# MCU.net
KiCad netlist of a schematic drawn in Altium Designer
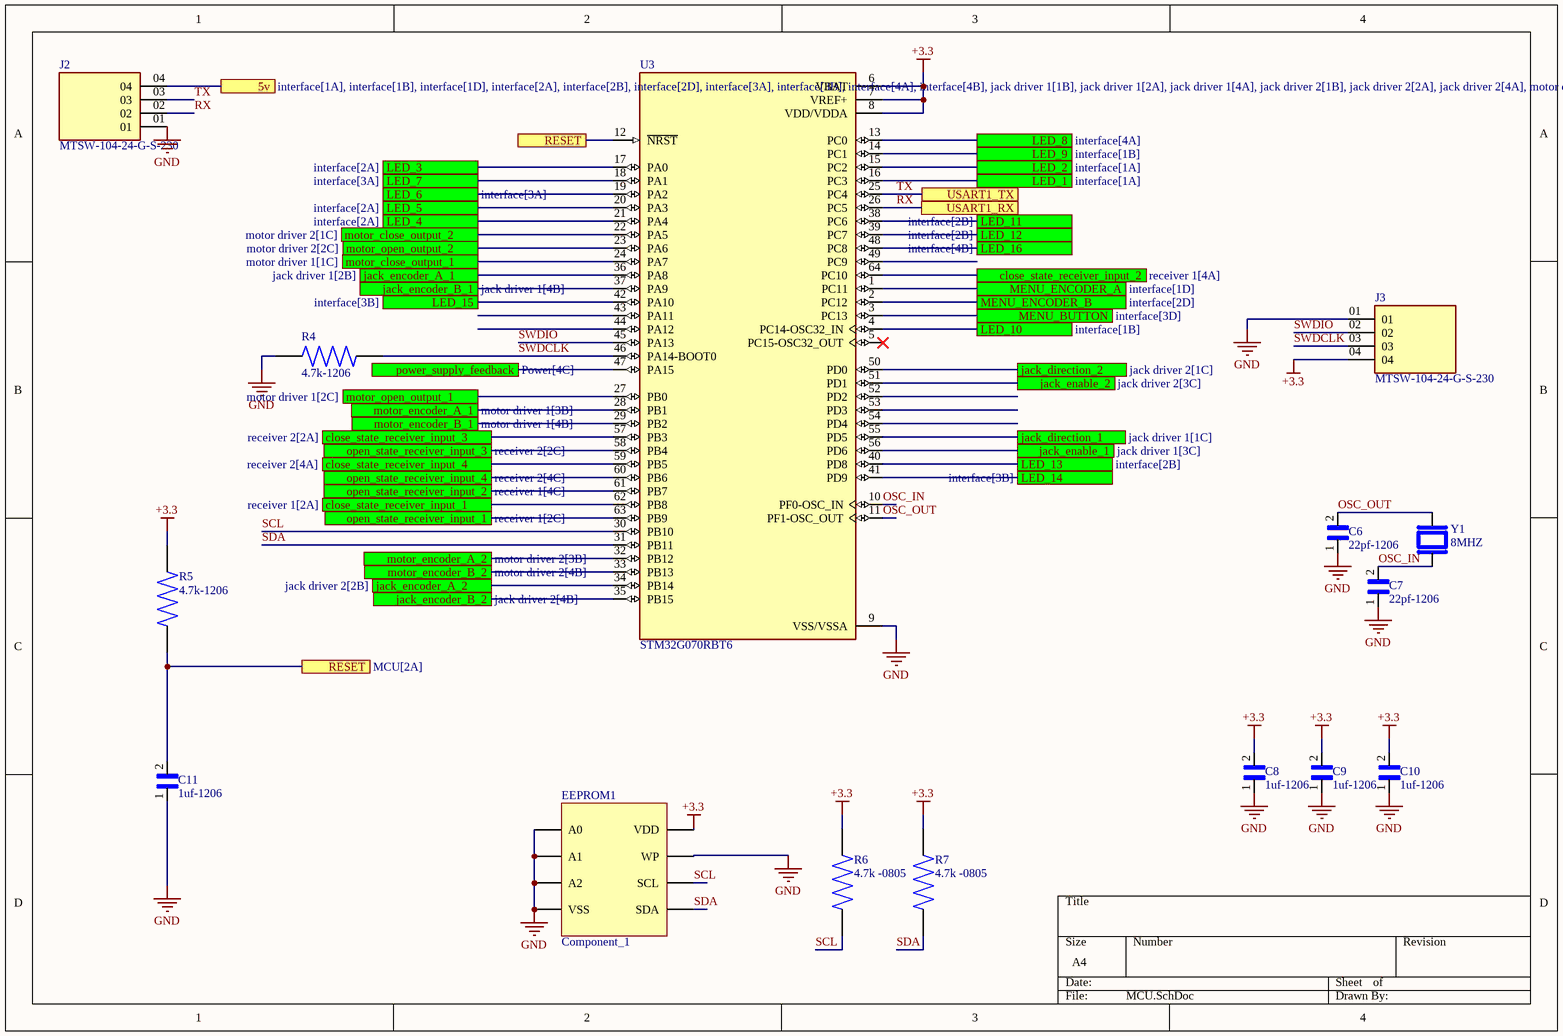
[diagram p0: MCU.SchDoc]

(export (version "E")
  (design (tool "Eeschema 10.0.6"))
  (components
    (comp (ref "C6")
      (value "22pf-1206")
      (footprint "CAPC3216X180N")
      (description "1ÂµF Â±20% 50V Ceramic Capacitor X8R 1206 (3216 Metric)")
      (fields (field (name "MF") "TDK") (field (name "MP") "CGA5L3X8R1H105M160AB"))
      (libsource (lib "cap-1206") (part "CGA5L3X8R1H105M160AB"))
    )
    (comp (ref "C7")
      (value "22pf-1206")
      (footprint "CAPC3216X180N")
      (description "1ÂµF Â±20% 50V Ceramic Capacitor X8R 1206 (3216 Metric)")
      (fields (field (name "MF") "TDK") (field (name "MP") "CGA5L3X8R1H105M160AB"))
      (libsource (lib "cap-1206") (part "CGA5L3X8R1H105M160AB"))
    )
    (comp (ref "C8")
      (value "1uf-1206")
      (footprint "CAPC3216X180N")
      (description "1ÂµF Â±20% 50V Ceramic Capacitor X8R 1206 (3216 Metric)")
      (fields (field (name "MF") "TDK") (field (name "MP") "CGA5L3X8R1H105M160AB"))
      (libsource (lib "cap-1206") (part "CGA5L3X8R1H105M160AB"))
    )
    (comp (ref "C9")
      (value "1uf-1206")
      (footprint "CAPC3216X180N")
      (description "1ÂµF Â±20% 50V Ceramic Capacitor X8R 1206 (3216 Metric)")
      (fields (field (name "MF") "TDK") (field (name "MP") "CGA5L3X8R1H105M160AB"))
      (libsource (lib "cap-1206") (part "CGA5L3X8R1H105M160AB"))
    )
    (comp (ref "C10")
      (value "1uf-1206")
      (footprint "CAPC3216X180N")
      (description "1ÂµF Â±20% 50V Ceramic Capacitor X8R 1206 (3216 Metric)")
      (fields (field (name "MF") "TDK") (field (name "MP") "CGA5L3X8R1H105M160AB"))
      (libsource (lib "cap-1206") (part "CGA5L3X8R1H105M160AB"))
    )
    (comp (ref "C11")
      (value "1uf-1206")
      (footprint "CAPC3216X180N")
      (description "1ÂµF Â±20% 50V Ceramic Capacitor X8R 1206 (3216 Metric)")
      (fields (field (name "MF") "TDK") (field (name "MP") "CGA5L3X8R1H105M160AB"))
      (libsource (lib "cap-1206") (part "CGA5L3X8R1H105M160AB"))
    )
    (comp (ref "EEPROM1")
      (value "Component_1")
      (footprint "SOIC127P602X172-8N")
      (libsource (lib "FM24CL64B") (part "Component_1"))
    )
    (comp (ref "J2")
      (value "MTSW-104-24-G-S-230")
      (footprint "SAMTEC_MTSW-104-24-G-S-230")
      (libsource (lib "4pin2.54mm") (part "MTSW-104-24-G-S-230"))
    )
    (comp (ref "J3")
      (value "MTSW-104-24-G-S-230")
      (footprint "SAMTEC_MTSW-104-24-G-S-230")
      (libsource (lib "") (part "MTSW-104-24-G-S-230_1"))
    )
    (comp (ref "R4")
      (value "4.7k-1206")
      (footprint "RESC3015X65N")
      (description "Res Thin Film 1206 10K Ohm 0.1% 1/8W Â±25ppm/Â°C Molded SMD SMD Paper T/R")
      (fields (field (name "MF") "TE Connectivity") (field (name "MP") "CPF1206B10KE1"))
      (libsource (lib "resistor-1206") (part "CPF1206B10KE1"))
    )
    (comp (ref "R5")
      (value "4.7k-1206")
      (footprint "RESC3015X65N")
      (description "Res Thin Film 1206 10K Ohm 0.1% 1/8W Â±25ppm/Â°C Molded SMD SMD Paper T/R")
      (fields (field (name "MF") "TE Connectivity") (field (name "MP") "CPF1206B10KE1"))
      (libsource (lib "resistor-1206") (part "CPF1206B10KE1"))
    )
    (comp (ref "R6")
      (value "4.7k -0805")
      (footprint "RESC2012X65N")
      (description "Fixed Resistor CRGCQ 0805 470R 5%")
      (fields (field (name "MF") "TE Connectivity") (field (name "MP") "CRGCQ0805J470R"))
      (libsource (lib "res0805") (part "CRGCQ0805J470R"))
    )
    (comp (ref "R7")
      (value "4.7k -0805")
      (footprint "RESC2012X65N")
      (description "Fixed Resistor CRGCQ 0805 470R 5%")
      (fields (field (name "MF") "TE Connectivity") (field (name "MP") "CRGCQ0805J470R"))
      (libsource (lib "res0805") (part "CRGCQ0805J470R"))
    )
    (comp (ref "U3")
      (value "STM32G070RBT6")
      (footprint "QFP50P1200X1200X160-64N")
      (fields (field (name "MF") "STMicroelectronics"))
      (libsource (lib "STM32G070RBT6") (part "STM32G070RBT6"))
    )
    (comp (ref "Y1")
      (value "8MHZ")
      (footprint "XTAL_ABLS2-12.000MHZ-D4Y-T")
      (description "HC/49US (AT49) LOW PROFILE SURFACE MOUNT MICROPROCESSOR CRYSTAL")
      (fields (field (name "MP") "ABLS2-12.000MHZ-D4Y-T") (field (name "MF") "Abracon"))
      (libsource (lib "CRYSTAL") (part "ABLS2-12.000MHZ-D4Y-T"))
    )
  )
  (nets
    (net (code "1") (name "+3.3") (class "Default")
      (node (ref "C10") (pin "2") (pinfunction "2_2") (pintype "passive"))
      (node (ref "C8") (pin "2") (pinfunction "2_2") (pintype "passive"))
      (node (ref "C9") (pin "2") (pinfunction "2_2") (pintype "passive"))
      (node (ref "EEPROM1") (pin "7") (pinfunction "VDD_7") (pintype "passive"))
      (node (ref "J3") (pin "04") (pinfunction "04_04") (pintype "passive"))
      (node (ref "R5") (pin "2") (pinfunction "2_2") (pintype "passive"))
      (node (ref "R6") (pin "2") (pinfunction "2_2") (pintype "passive"))
      (node (ref "R7") (pin "2") (pinfunction "2_2") (pintype "passive"))
      (node (ref "U3") (pin "6") (pinfunction "VBAT_6") (pintype "power_in"))
      (node (ref "U3") (pin "7") (pinfunction "VREF+_7") (pintype "power_in"))
      (node (ref "U3") (pin "8") (pinfunction "VDD/VDDA_8") (pintype "power_in"))
    )
    (net (code "2") (name "/5v") (class "Default")
      (node (ref "J2") (pin "04") (pinfunction "04_04") (pintype "passive"))
    )
    (net (code "3") (name "/LED_1") (class "Default")
      (node (ref "U3") (pin "16") (pinfunction "PC3_16") (pintype "bidirectional"))
    )
    (net (code "4") (name "/LED_2") (class "Default")
      (node (ref "U3") (pin "15") (pinfunction "PC2_15") (pintype "bidirectional"))
    )
    (net (code "5") (name "/LED_3") (class "Default")
      (node (ref "U3") (pin "17") (pinfunction "PA0_17") (pintype "bidirectional"))
    )
    (net (code "6") (name "/LED_4") (class "Default")
      (node (ref "U3") (pin "21") (pinfunction "PA4_21") (pintype "bidirectional"))
    )
    (net (code "7") (name "/LED_5") (class "Default")
      (node (ref "U3") (pin "20") (pinfunction "PA3_20") (pintype "bidirectional"))
    )
    (net (code "8") (name "/LED_6") (class "Default")
      (node (ref "U3") (pin "19") (pinfunction "PA2_19") (pintype "bidirectional"))
    )
    (net (code "9") (name "/LED_7") (class "Default")
      (node (ref "U3") (pin "18") (pinfunction "PA1_18") (pintype "bidirectional"))
    )
    (net (code "10") (name "/LED_8") (class "Default")
      (node (ref "U3") (pin "13") (pinfunction "PC0_13") (pintype "bidirectional"))
    )
    (net (code "11") (name "/LED_9") (class "Default")
      (node (ref "U3") (pin "14") (pinfunction "PC1_14") (pintype "bidirectional"))
    )
    (net (code "12") (name "/LED_10") (class "Default")
      (node (ref "U3") (pin "4") (pinfunction "PC14-OSC32_IN_4") (pintype "bidirectional"))
    )
    (net (code "13") (name "/LED_11") (class "Default")
      (node (ref "U3") (pin "38") (pinfunction "PC6_38") (pintype "bidirectional"))
    )
    (net (code "14") (name "/LED_12") (class "Default")
      (node (ref "U3") (pin "39") (pinfunction "PC7_39") (pintype "bidirectional"))
    )
    (net (code "15") (name "/LED_13") (class "Default")
      (node (ref "U3") (pin "40") (pinfunction "PD8_40") (pintype "bidirectional"))
    )
    (net (code "16") (name "/LED_14") (class "Default")
      (node (ref "U3") (pin "41") (pinfunction "PD9_41") (pintype "bidirectional"))
    )
    (net (code "17") (name "/LED_15") (class "Default")
      (node (ref "U3") (pin "42") (pinfunction "PA10_42") (pintype "bidirectional"))
    )
    (net (code "18") (name "/LED_16") (class "Default")
      (node (ref "U3") (pin "48") (pinfunction "PC8_48") (pintype "bidirectional"))
    )
    (net (code "19") (name "/MENU_BUTTON") (class "Default")
      (node (ref "U3") (pin "3") (pinfunction "PC13_3") (pintype "bidirectional"))
    )
    (net (code "20") (name "/MENU_ENCODER_A") (class "Default")
      (node (ref "U3") (pin "1") (pinfunction "PC11_1") (pintype "bidirectional"))
    )
    (net (code "21") (name "/MENU_ENCODER_B") (class "Default")
      (node (ref "U3") (pin "2") (pinfunction "PC12_2") (pintype "bidirectional"))
    )
    (net (code "22") (name "/OSC_IN") (class "Default")
      (node (ref "C7") (pin "2") (pinfunction "2_2") (pintype "passive"))
      (node (ref "U3") (pin "10") (pinfunction "PF0-OSC_IN_10") (pintype "bidirectional"))
      (node (ref "Y1") (pin "1") (pinfunction "1_1") (pintype "passive"))
    )
    (net (code "23") (name "/OSC_OUT") (class "Default")
      (node (ref "C6") (pin "2") (pinfunction "2_2") (pintype "passive"))
      (node (ref "U3") (pin "11") (pinfunction "PF1-OSC_OUT_11") (pintype "bidirectional"))
      (node (ref "Y1") (pin "2") (pinfunction "2_2") (pintype "passive"))
    )
    (net (code "24") (name "/RESET") (class "Default")
      (node (ref "C11") (pin "2") (pinfunction "2_2") (pintype "passive"))
      (node (ref "R5") (pin "1") (pinfunction "1_1") (pintype "passive"))
      (node (ref "U3") (pin "12") (pinfunction "~{NRST}_12") (pintype "input"))
    )
    (net (code "25") (name "/RX") (class "Default")
      (node (ref "J2") (pin "02") (pinfunction "02_02") (pintype "passive"))
      (node (ref "U3") (pin "26") (pinfunction "PC5_26") (pintype "bidirectional"))
    )
    (net (code "26") (name "/SCL") (class "Default")
      (node (ref "EEPROM1") (pin "5") (pinfunction "SCL_5") (pintype "passive"))
      (node (ref "R6") (pin "1") (pinfunction "1_1") (pintype "passive"))
      (node (ref "U3") (pin "30") (pinfunction "PB10_30") (pintype "bidirectional"))
    )
    (net (code "27") (name "/SDA") (class "Default")
      (node (ref "EEPROM1") (pin "4") (pinfunction "SDA_4") (pintype "passive"))
      (node (ref "R7") (pin "1") (pinfunction "1_1") (pintype "passive"))
      (node (ref "U3") (pin "31") (pinfunction "PB11_31") (pintype "bidirectional"))
    )
    (net (code "28") (name "/SWDCLK") (class "Default")
      (node (ref "J3") (pin "03") (pinfunction "03_03") (pintype "passive"))
      (node (ref "R4") (pin "1") (pinfunction "1_1") (pintype "passive"))
      (node (ref "U3") (pin "46") (pinfunction "PA14-BOOT0_46") (pintype "bidirectional"))
    )
    (net (code "29") (name "/SWDIO") (class "Default")
      (node (ref "J3") (pin "02") (pinfunction "02_02") (pintype "passive"))
      (node (ref "U3") (pin "45") (pinfunction "PA13_45") (pintype "bidirectional"))
    )
    (net (code "30") (name "/TX") (class "Default")
      (node (ref "J2") (pin "03") (pinfunction "03_03") (pintype "passive"))
      (node (ref "U3") (pin "25") (pinfunction "PC4_25") (pintype "bidirectional"))
    )
    (net (code "31") (name "/close_state_receiver_input_1") (class "Default")
      (node (ref "U3") (pin "62") (pinfunction "PB8_62") (pintype "bidirectional"))
    )
    (net (code "32") (name "/close_state_receiver_input_2") (class "Default")
      (node (ref "U3") (pin "64") (pinfunction "PC10_64") (pintype "bidirectional"))
    )
    (net (code "33") (name "/close_state_receiver_input_3") (class "Default")
      (node (ref "U3") (pin "57") (pinfunction "PB3_57") (pintype "bidirectional"))
    )
    (net (code "34") (name "/close_state_receiver_input_4") (class "Default")
      (node (ref "U3") (pin "59") (pinfunction "PB5_59") (pintype "bidirectional"))
    )
    (net (code "35") (name "/jack_direction_1") (class "Default")
      (node (ref "U3") (pin "55") (pinfunction "PD5_55") (pintype "bidirectional"))
    )
    (net (code "36") (name "/jack_direction_2") (class "Default")
      (node (ref "U3") (pin "50") (pinfunction "PD0_50") (pintype "bidirectional"))
    )
    (net (code "37") (name "/jack_enable_1") (class "Default")
      (node (ref "U3") (pin "56") (pinfunction "PD6_56") (pintype "bidirectional"))
    )
    (net (code "38") (name "/jack_enable_2") (class "Default")
      (node (ref "U3") (pin "51") (pinfunction "PD1_51") (pintype "bidirectional"))
    )
    (net (code "39") (name "/jack_encoder_A_1") (class "Default")
      (node (ref "U3") (pin "36") (pinfunction "PA8_36") (pintype "bidirectional"))
    )
    (net (code "40") (name "/jack_encoder_A_2") (class "Default")
      (node (ref "U3") (pin "34") (pinfunction "PB14_34") (pintype "bidirectional"))
    )
    (net (code "41") (name "/jack_encoder_B_1") (class "Default")
      (node (ref "U3") (pin "37") (pinfunction "PA9_37") (pintype "bidirectional"))
    )
    (net (code "42") (name "/jack_encoder_B_2") (class "Default")
      (node (ref "U3") (pin "35") (pinfunction "PB15_35") (pintype "bidirectional"))
    )
    (net (code "43") (name "/motor_close_output_1") (class "Default")
      (node (ref "U3") (pin "24") (pinfunction "PA7_24") (pintype "bidirectional"))
    )
    (net (code "44") (name "/motor_close_output_2") (class "Default")
      (node (ref "U3") (pin "22") (pinfunction "PA5_22") (pintype "bidirectional"))
    )
    (net (code "45") (name "/motor_encoder_A_1") (class "Default")
      (node (ref "U3") (pin "28") (pinfunction "PB1_28") (pintype "bidirectional"))
    )
    (net (code "46") (name "/motor_encoder_A_2") (class "Default")
      (node (ref "U3") (pin "32") (pinfunction "PB12_32") (pintype "bidirectional"))
    )
    (net (code "47") (name "/motor_encoder_B_1") (class "Default")
      (node (ref "U3") (pin "29") (pinfunction "PB2_29") (pintype "bidirectional"))
    )
    (net (code "48") (name "/motor_encoder_B_2") (class "Default")
      (node (ref "U3") (pin "33") (pinfunction "PB13_33") (pintype "bidirectional"))
    )
    (net (code "49") (name "/motor_open_output_1") (class "Default")
      (node (ref "U3") (pin "27") (pinfunction "PB0_27") (pintype "bidirectional"))
    )
    (net (code "50") (name "/motor_open_output_2") (class "Default")
      (node (ref "U3") (pin "23") (pinfunction "PA6_23") (pintype "bidirectional"))
    )
    (net (code "51") (name "/open_state_receiver_input_1") (class "Default")
      (node (ref "U3") (pin "63") (pinfunction "PB9_63") (pintype "bidirectional"))
    )
    (net (code "52") (name "/open_state_receiver_input_2") (class "Default")
      (node (ref "U3") (pin "61") (pinfunction "PB7_61") (pintype "bidirectional"))
    )
    (net (code "53") (name "/open_state_receiver_input_3") (class "Default")
      (node (ref "U3") (pin "58") (pinfunction "PB4_58") (pintype "bidirectional"))
    )
    (net (code "54") (name "/open_state_receiver_input_4") (class "Default")
      (node (ref "U3") (pin "60") (pinfunction "PB6_60") (pintype "bidirectional"))
    )
    (net (code "55") (name "/power_supply_feedback") (class "Default")
      (node (ref "U3") (pin "47") (pinfunction "PA15_47") (pintype "bidirectional"))
    )
    (net (code "56") (name "GND") (class "Default")
      (node (ref "C10") (pin "1") (pinfunction "1_1") (pintype "passive"))
      (node (ref "C11") (pin "1") (pinfunction "1_1") (pintype "passive"))
      (node (ref "C6") (pin "1") (pinfunction "1_1") (pintype "passive"))
      (node (ref "C7") (pin "1") (pinfunction "1_1") (pintype "passive"))
      (node (ref "C8") (pin "1") (pinfunction "1_1") (pintype "passive"))
      (node (ref "C9") (pin "1") (pinfunction "1_1") (pintype "passive"))
      (node (ref "EEPROM1") (pin "0") (pinfunction "A0_0") (pintype "passive"))
      (node (ref "EEPROM1") (pin "1") (pinfunction "A1_1") (pintype "passive"))
      (node (ref "EEPROM1") (pin "2") (pinfunction "A2_2") (pintype "passive"))
      (node (ref "EEPROM1") (pin "3") (pinfunction "VSS_3") (pintype "passive"))
      (node (ref "EEPROM1") (pin "6") (pinfunction "WP_6") (pintype "passive"))
      (node (ref "J2") (pin "01") (pinfunction "01_01") (pintype "passive"))
      (node (ref "J3") (pin "01") (pinfunction "01_01") (pintype "passive"))
      (node (ref "R4") (pin "2") (pinfunction "2_2") (pintype "passive"))
      (node (ref "U3") (pin "9") (pinfunction "VSS/VSSA_9") (pintype "power_in"))
    )
    (net (code "57") (name "unconnected-(U3-PA11-Pad43)") (class "Default")
      (node (ref "U3") (pin "43") (pinfunction "PA11_43") (pintype "bidirectional"))
    )
    (net (code "58") (name "unconnected-(U3-PA12-Pad44)") (class "Default")
      (node (ref "U3") (pin "44") (pinfunction "PA12_44") (pintype "bidirectional"))
    )
    (net (code "59") (name "unconnected-(U3-PC9-Pad49)") (class "Default")
      (node (ref "U3") (pin "49") (pinfunction "PC9_49") (pintype "bidirectional"))
    )
    (net (code "60") (name "unconnected-(U3-PC15-OSC32_OUT-Pad5)") (class "Default")
      (node (ref "U3") (pin "5") (pinfunction "PC15-OSC32_OUT_5") (pintype "bidirectional+no_connect"))
    )
    (net (code "61") (name "unconnected-(U3-PD2-Pad52)") (class "Default")
      (node (ref "U3") (pin "52") (pinfunction "PD2_52") (pintype "bidirectional"))
    )
    (net (code "62") (name "unconnected-(U3-PD3-Pad53)") (class "Default")
      (node (ref "U3") (pin "53") (pinfunction "PD3_53") (pintype "bidirectional"))
    )
    (net (code "63") (name "unconnected-(U3-PD4-Pad54)") (class "Default")
      (node (ref "U3") (pin "54") (pinfunction "PD4_54") (pintype "bidirectional"))
    )
  )
)
